# psu_and_discharge.net
KiCad netlist of a schematic drawn in Altium Designer
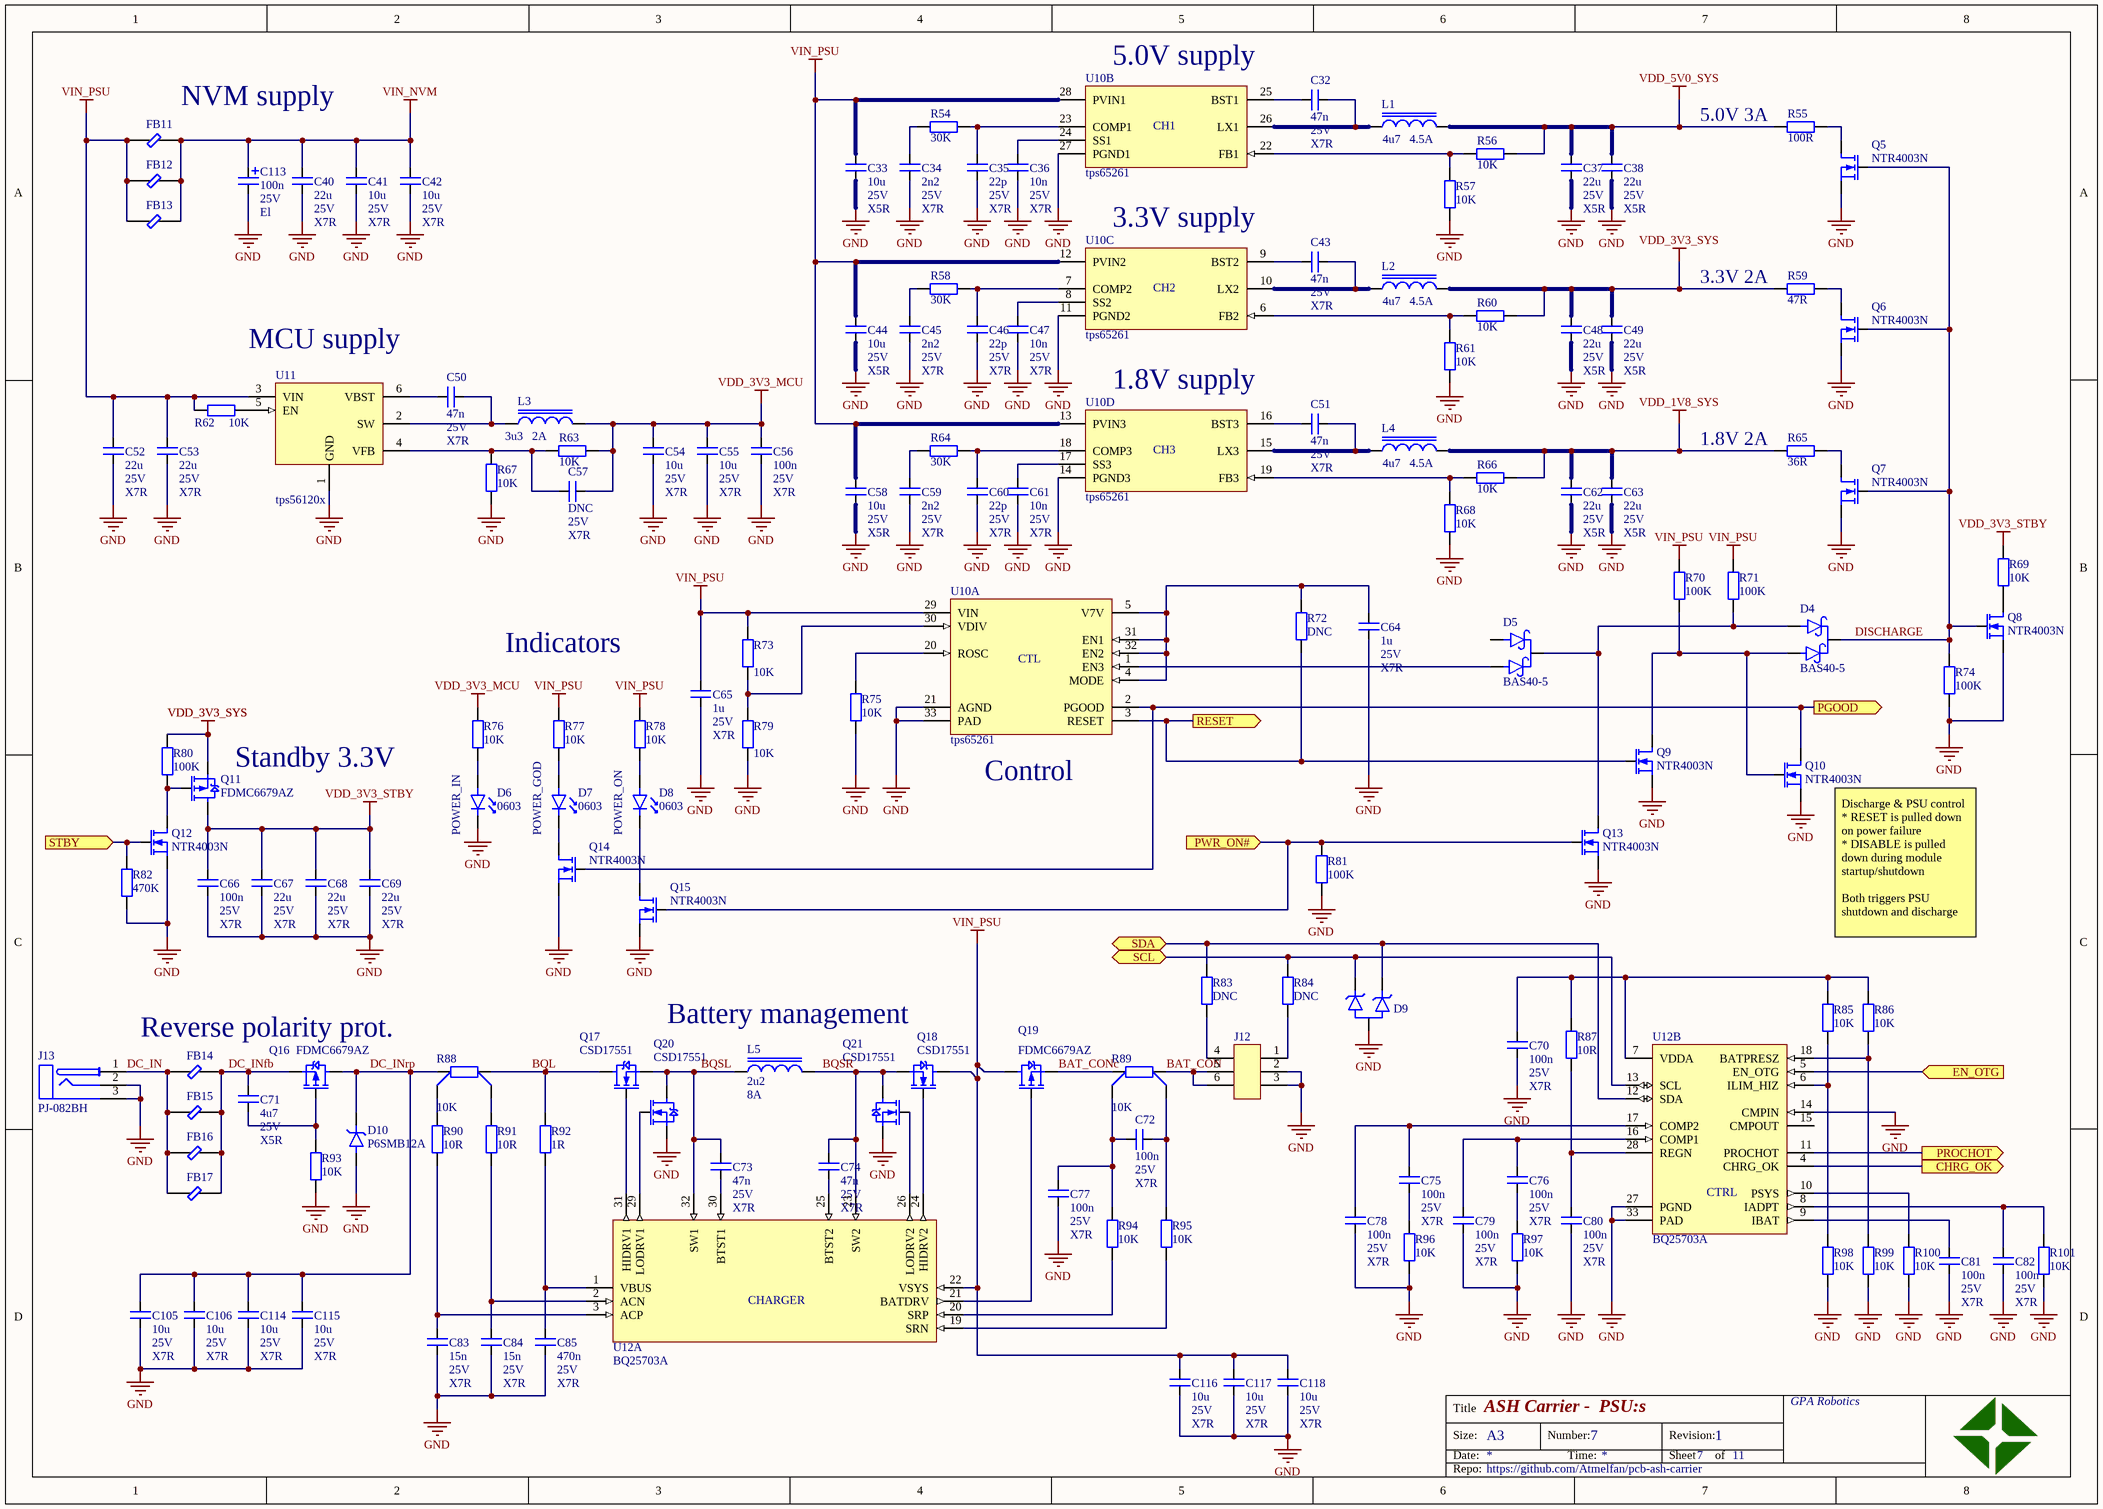
[diagram p0: psu_and_discharge.SchDoc]

(export (version "E")
  (design (tool "Eeschema 10.0.6"))
  (components
    (comp (ref "C32")
      (value "47n")
      (footprint "C1005[0402]")
      (description "Capacitor")
      (fields (field (name "VOLTAGE") "25V") (field (name "TYPE") "X7R") (field (name "Comment") "cap"))
      (libsource (lib "gpa_passives") (part "cap"))
    )
    (comp (ref "C33")
      (value "10u")
      (footprint "C3216[1206]")
      (description "Capacitor")
      (fields (field (name "VOLTAGE") "25V") (field (name "TYPE") "X5R") (field (name "Comment") "cap"))
      (libsource (lib "gpa_passives") (part "cap"))
    )
    (comp (ref "C34")
      (value "2n2")
      (footprint "C1005[0402]")
      (description "Capacitor")
      (fields (field (name "VOLTAGE") "25V") (field (name "TYPE") "X7R") (field (name "Comment") "cap"))
      (libsource (lib "gpa_passives") (part "cap"))
    )
    (comp (ref "C35")
      (value "22p")
      (footprint "C1005[0402]")
      (description "Capacitor")
      (fields (field (name "VOLTAGE") "25V") (field (name "TYPE") "X7R") (field (name "Comment") "cap"))
      (libsource (lib "gpa_passives") (part "cap"))
    )
    (comp (ref "C36")
      (value "10n")
      (footprint "C1005[0402]")
      (description "Capacitor")
      (fields (field (name "VOLTAGE") "25V") (field (name "TYPE") "X7R") (field (name "Comment") "cap"))
      (libsource (lib "gpa_passives") (part "cap"))
    )
    (comp (ref "C37")
      (value "22u")
      (footprint "C3216[1206]")
      (description "Capacitor")
      (fields (field (name "VOLTAGE") "25V") (field (name "TYPE") "X5R") (field (name "Comment") "cap"))
      (libsource (lib "gpa_passives") (part "cap"))
    )
    (comp (ref "C38")
      (value "22u")
      (footprint "C3216[1206]")
      (description "Capacitor")
      (fields (field (name "VOLTAGE") "25V") (field (name "TYPE") "X5R") (field (name "Comment") "cap"))
      (libsource (lib "gpa_passives") (part "cap"))
    )
    (comp (ref "C40")
      (value "22u")
      (footprint "C3216[1206]")
      (description "Capacitor")
      (fields (field (name "VOLTAGE") "25V") (field (name "TYPE") "X7R") (field (name "Comment") "cap"))
      (libsource (lib "gpa_passives") (part "cap"))
    )
    (comp (ref "C41")
      (value "10u")
      (footprint "C3216[1206]")
      (description "Capacitor")
      (fields (field (name "VOLTAGE") "25V") (field (name "TYPE") "X7R") (field (name "Comment") "cap"))
      (libsource (lib "gpa_passives") (part "cap"))
    )
    (comp (ref "C42")
      (value "10u")
      (footprint "C3216[1206]")
      (description "Capacitor")
      (fields (field (name "VOLTAGE") "25V") (field (name "TYPE") "X7R") (field (name "Comment") "cap"))
      (libsource (lib "gpa_passives") (part "cap"))
    )
    (comp (ref "C43")
      (value "47n")
      (footprint "C1005[0402]")
      (description "Capacitor")
      (fields (field (name "VOLTAGE") "25V") (field (name "TYPE") "X7R") (field (name "Comment") "cap"))
      (libsource (lib "gpa_passives") (part "cap"))
    )
    (comp (ref "C44")
      (value "10u")
      (footprint "C3216[1206]")
      (description "Capacitor")
      (fields (field (name "VOLTAGE") "25V") (field (name "TYPE") "X5R") (field (name "Comment") "cap"))
      (libsource (lib "gpa_passives") (part "cap"))
    )
    (comp (ref "C45")
      (value "2n2")
      (footprint "C1005[0402]")
      (description "Capacitor")
      (fields (field (name "VOLTAGE") "25V") (field (name "TYPE") "X7R") (field (name "Comment") "cap"))
      (libsource (lib "gpa_passives") (part "cap"))
    )
    (comp (ref "C46")
      (value "22p")
      (footprint "C1005[0402]")
      (description "Capacitor")
      (fields (field (name "VOLTAGE") "25V") (field (name "TYPE") "X7R") (field (name "Comment") "cap"))
      (libsource (lib "gpa_passives") (part "cap"))
    )
    (comp (ref "C47")
      (value "10n")
      (footprint "C1005[0402]")
      (description "Capacitor")
      (fields (field (name "VOLTAGE") "25V") (field (name "TYPE") "X7R") (field (name "Comment") "cap"))
      (libsource (lib "gpa_passives") (part "cap"))
    )
    (comp (ref "C48")
      (value "22u")
      (footprint "C3216[1206]")
      (description "Capacitor")
      (fields (field (name "VOLTAGE") "25V") (field (name "TYPE") "X5R") (field (name "Comment") "cap"))
      (libsource (lib "gpa_passives") (part "cap"))
    )
    (comp (ref "C49")
      (value "22u")
      (footprint "C3216[1206]")
      (description "Capacitor")
      (fields (field (name "VOLTAGE") "25V") (field (name "TYPE") "X5R") (field (name "Comment") "cap"))
      (libsource (lib "gpa_passives") (part "cap"))
    )
    (comp (ref "C50")
      (value "47n")
      (footprint "C1005[0402]")
      (description "Capacitor")
      (fields (field (name "VOLTAGE") "25V") (field (name "TYPE") "X7R") (field (name "Comment") "cap"))
      (libsource (lib "gpa_passives") (part "cap"))
    )
    (comp (ref "C51")
      (value "47n")
      (footprint "C1005[0402]")
      (description "Capacitor")
      (fields (field (name "VOLTAGE") "25V") (field (name "TYPE") "X7R") (field (name "Comment") "cap"))
      (libsource (lib "gpa_passives") (part "cap"))
    )
    (comp (ref "C52")
      (value "22u")
      (footprint "C3216[1206]")
      (description "Capacitor")
      (fields (field (name "VOLTAGE") "25V") (field (name "TYPE") "X7R") (field (name "Comment") "cap"))
      (libsource (lib "gpa_passives") (part "cap"))
    )
    (comp (ref "C53")
      (value "22u")
      (footprint "C3216[1206]")
      (description "Capacitor")
      (fields (field (name "VOLTAGE") "25V") (field (name "TYPE") "X7R") (field (name "Comment") "cap"))
      (libsource (lib "gpa_passives") (part "cap"))
    )
    (comp (ref "C54")
      (value "10u")
      (footprint "C3216[1206]")
      (description "Capacitor")
      (fields (field (name "VOLTAGE") "25V") (field (name "TYPE") "X7R") (field (name "Comment") "cap"))
      (libsource (lib "gpa_passives") (part "cap"))
    )
    (comp (ref "C55")
      (value "10u")
      (footprint "C3216[1206]")
      (description "Capacitor")
      (fields (field (name "VOLTAGE") "25V") (field (name "TYPE") "X7R") (field (name "Comment") "cap"))
      (libsource (lib "gpa_passives") (part "cap"))
    )
    (comp (ref "C56")
      (value "100n")
      (footprint "C1005[0402]")
      (description "Capacitor")
      (fields (field (name "VOLTAGE") "25V") (field (name "TYPE") "X7R") (field (name "Comment") "cap"))
      (libsource (lib "gpa_passives") (part "cap"))
    )
    (comp (ref "C57")
      (value "DNC")
      (footprint "C1005[0402]")
      (description "Capacitor")
      (fields (field (name "VOLTAGE") "25V") (field (name "TYPE") "X7R") (field (name "Comment") "cap"))
      (libsource (lib "gpa_passives") (part "cap"))
    )
    (comp (ref "C58")
      (value "10u")
      (footprint "C3216[1206]")
      (description "Capacitor")
      (fields (field (name "VOLTAGE") "25V") (field (name "TYPE") "X5R") (field (name "Comment") "cap"))
      (libsource (lib "gpa_passives") (part "cap"))
    )
    (comp (ref "C59")
      (value "2n2")
      (footprint "C1005[0402]")
      (description "Capacitor")
      (fields (field (name "VOLTAGE") "25V") (field (name "TYPE") "X7R") (field (name "Comment") "cap"))
      (libsource (lib "gpa_passives") (part "cap"))
    )
    (comp (ref "C60")
      (value "22p")
      (footprint "C1005[0402]")
      (description "Capacitor")
      (fields (field (name "VOLTAGE") "25V") (field (name "TYPE") "X7R") (field (name "Comment") "cap"))
      (libsource (lib "gpa_passives") (part "cap"))
    )
    (comp (ref "C61")
      (value "10n")
      (footprint "C1005[0402]")
      (description "Capacitor")
      (fields (field (name "VOLTAGE") "25V") (field (name "TYPE") "X7R") (field (name "Comment") "cap"))
      (libsource (lib "gpa_passives") (part "cap"))
    )
    (comp (ref "C62")
      (value "22u")
      (footprint "C3216[1206]")
      (description "Capacitor")
      (fields (field (name "VOLTAGE") "25V") (field (name "TYPE") "X5R") (field (name "Comment") "cap"))
      (libsource (lib "gpa_passives") (part "cap"))
    )
    (comp (ref "C63")
      (value "22u")
      (footprint "C3216[1206]")
      (description "Capacitor")
      (fields (field (name "VOLTAGE") "25V") (field (name "TYPE") "X5R") (field (name "Comment") "cap"))
      (libsource (lib "gpa_passives") (part "cap"))
    )
    (comp (ref "C64")
      (value "1u")
      (footprint "C2012[0805]")
      (description "Capacitor")
      (fields (field (name "VOLTAGE") "25V") (field (name "TYPE") "X7R") (field (name "Comment") "cap"))
      (libsource (lib "gpa_passives") (part "cap"))
    )
    (comp (ref "C65")
      (value "1u")
      (footprint "C2012[0805]")
      (description "Capacitor")
      (fields (field (name "VOLTAGE") "25V") (field (name "TYPE") "X7R") (field (name "Comment") "cap"))
      (libsource (lib "gpa_passives") (part "cap"))
    )
    (comp (ref "C66")
      (value "100n")
      (footprint "C1005[0402]")
      (description "Capacitor")
      (fields (field (name "VOLTAGE") "25V") (field (name "TYPE") "X7R") (field (name "Comment") "cap"))
      (libsource (lib "gpa_passives") (part "cap"))
    )
    (comp (ref "C67")
      (value "22u")
      (footprint "C3216[1206]")
      (description "Capacitor")
      (fields (field (name "VOLTAGE") "25V") (field (name "TYPE") "X7R") (field (name "Comment") "cap"))
      (libsource (lib "gpa_passives") (part "cap"))
    )
    (comp (ref "C68")
      (value "22u")
      (footprint "C3216[1206]")
      (description "Capacitor")
      (fields (field (name "VOLTAGE") "25V") (field (name "TYPE") "X7R") (field (name "Comment") "cap"))
      (libsource (lib "gpa_passives") (part "cap"))
    )
    (comp (ref "C69")
      (value "22u")
      (footprint "C3216[1206]")
      (description "Capacitor")
      (fields (field (name "VOLTAGE") "25V") (field (name "TYPE") "X7R") (field (name "Comment") "cap"))
      (libsource (lib "gpa_passives") (part "cap"))
    )
    (comp (ref "C70")
      (value "100n")
      (footprint "C1005[0402]")
      (description "Capacitor")
      (fields (field (name "VOLTAGE") "25V") (field (name "TYPE") "X7R") (field (name "Comment") "cap"))
      (libsource (lib "gpa_passives") (part "cap"))
    )
    (comp (ref "C71")
      (value "4u7")
      (footprint "C1005[0402]")
      (description "Capacitor")
      (fields (field (name "VOLTAGE") "25V") (field (name "TYPE") "X5R") (field (name "Comment") "cap"))
      (libsource (lib "gpa_passives") (part "cap"))
    )
    (comp (ref "C72")
      (value "100n")
      (footprint "C1005[0402]")
      (description "Capacitor")
      (fields (field (name "VOLTAGE") "25V") (field (name "TYPE") "X7R") (field (name "Comment") "cap"))
      (libsource (lib "gpa_passives") (part "cap"))
    )
    (comp (ref "C73")
      (value "47n")
      (footprint "C1005[0402]")
      (description "Capacitor")
      (fields (field (name "VOLTAGE") "25V") (field (name "TYPE") "X7R") (field (name "Comment") "cap"))
      (libsource (lib "gpa_passives") (part "cap"))
    )
    (comp (ref "C74")
      (value "47n")
      (footprint "C1005[0402]")
      (description "Capacitor")
      (fields (field (name "VOLTAGE") "25V") (field (name "TYPE") "X7R") (field (name "Comment") "cap"))
      (libsource (lib "gpa_passives") (part "cap"))
    )
    (comp (ref "C75")
      (value "100n")
      (footprint "C1005[0402]")
      (description "Capacitor")
      (fields (field (name "VOLTAGE") "25V") (field (name "TYPE") "X7R") (field (name "Comment") "cap"))
      (libsource (lib "gpa_passives") (part "cap"))
    )
    (comp (ref "C76")
      (value "100n")
      (footprint "C1005[0402]")
      (description "Capacitor")
      (fields (field (name "VOLTAGE") "25V") (field (name "TYPE") "X7R") (field (name "Comment") "cap"))
      (libsource (lib "gpa_passives") (part "cap"))
    )
    (comp (ref "C77")
      (value "100n")
      (footprint "C1005[0402]")
      (description "Capacitor")
      (fields (field (name "VOLTAGE") "25V") (field (name "TYPE") "X7R") (field (name "Comment") "cap"))
      (libsource (lib "gpa_passives") (part "cap"))
    )
    (comp (ref "C78")
      (value "100n")
      (footprint "C1005[0402]")
      (description "Capacitor")
      (fields (field (name "VOLTAGE") "25V") (field (name "TYPE") "X7R") (field (name "Comment") "cap"))
      (libsource (lib "gpa_passives") (part "cap"))
    )
    (comp (ref "C79")
      (value "100n")
      (footprint "C1005[0402]")
      (description "Capacitor")
      (fields (field (name "VOLTAGE") "25V") (field (name "TYPE") "X7R") (field (name "Comment") "cap"))
      (libsource (lib "gpa_passives") (part "cap"))
    )
    (comp (ref "C80")
      (value "100n")
      (footprint "C1005[0402]")
      (description "Capacitor")
      (fields (field (name "VOLTAGE") "25V") (field (name "TYPE") "X7R") (field (name "Comment") "cap"))
      (libsource (lib "gpa_passives") (part "cap"))
    )
    (comp (ref "C81")
      (value "100n")
      (footprint "C1005[0402]")
      (description "Capacitor")
      (fields (field (name "VOLTAGE") "25V") (field (name "TYPE") "X7R") (field (name "Comment") "cap"))
      (libsource (lib "gpa_passives") (part "cap"))
    )
    (comp (ref "C82")
      (value "100n")
      (footprint "C1005[0402]")
      (description "Capacitor")
      (fields (field (name "VOLTAGE") "25V") (field (name "TYPE") "X7R") (field (name "Comment") "cap"))
      (libsource (lib "gpa_passives") (part "cap"))
    )
    (comp (ref "C83")
      (value "15n")
      (footprint "C1005[0402]")
      (description "Capacitor")
      (fields (field (name "VOLTAGE") "25V") (field (name "TYPE") "X7R") (field (name "Comment") "cap"))
      (libsource (lib "gpa_passives") (part "cap"))
    )
    (comp (ref "C84")
      (value "15n")
      (footprint "C1005[0402]")
      (description "Capacitor")
      (fields (field (name "VOLTAGE") "25V") (field (name "TYPE") "X7R") (field (name "Comment") "cap"))
      (libsource (lib "gpa_passives") (part "cap"))
    )
    (comp (ref "C85")
      (value "470n")
      (footprint "C1005[0402]")
      (description "Capacitor")
      (fields (field (name "VOLTAGE") "25V") (field (name "TYPE") "X7R") (field (name "Comment") "cap"))
      (libsource (lib "gpa_passives") (part "cap"))
    )
    (comp (ref "C105")
      (value "10u")
      (footprint "C3216[1206]")
      (description "Capacitor")
      (fields (field (name "VOLTAGE") "25V") (field (name "TYPE") "X7R") (field (name "Comment") "cap"))
      (libsource (lib "gpa_passives") (part "cap"))
    )
    (comp (ref "C106")
      (value "10u")
      (footprint "C3216[1206]")
      (description "Capacitor")
      (fields (field (name "VOLTAGE") "25V") (field (name "TYPE") "X7R") (field (name "Comment") "cap"))
      (libsource (lib "gpa_passives") (part "cap"))
    )
    (comp (ref "C113")
      (value "100n")
      (footprint "CAPAE7366X55M")
      (description "Polarized capacitor")
      (fields (field (name "VOLTAGE") "25V") (field (name "TYPE") "El") (field (name "Comment") "pcap"))
      (libsource (lib "gpa_passives") (part "pcap"))
    )
    (comp (ref "C114")
      (value "10u")
      (footprint "C3216[1206]")
      (description "Capacitor")
      (fields (field (name "VOLTAGE") "25V") (field (name "TYPE") "X7R") (field (name "Comment") "cap"))
      (libsource (lib "gpa_passives") (part "cap"))
    )
    (comp (ref "C115")
      (value "10u")
      (footprint "C3216[1206]")
      (description "Capacitor")
      (fields (field (name "VOLTAGE") "25V") (field (name "TYPE") "X7R") (field (name "Comment") "cap"))
      (libsource (lib "gpa_passives") (part "cap"))
    )
    (comp (ref "C116")
      (value "10u")
      (footprint "C3216[1206]")
      (description "Capacitor")
      (fields (field (name "VOLTAGE") "25V") (field (name "TYPE") "X7R") (field (name "Comment") "cap"))
      (libsource (lib "gpa_passives") (part "cap"))
    )
    (comp (ref "C117")
      (value "10u")
      (footprint "C3216[1206]")
      (description "Capacitor")
      (fields (field (name "VOLTAGE") "25V") (field (name "TYPE") "X7R") (field (name "Comment") "cap"))
      (libsource (lib "gpa_passives") (part "cap"))
    )
    (comp (ref "C118")
      (value "10u")
      (footprint "C3216[1206]")
      (description "Capacitor")
      (fields (field (name "VOLTAGE") "25V") (field (name "TYPE") "X7R") (field (name "Comment") "cap"))
      (libsource (lib "gpa_passives") (part "cap"))
    )
    (comp (ref "D4")
      (value "BAS40-5")
      (footprint "DCC_SOT95P235X110-3N")
      (libsource (lib "gpa_actives") (part "diode_dual_cc"))
    )
    (comp (ref "D5")
      (value "BAS40-5")
      (footprint "DCC_SOT95P235X110-3N")
      (libsource (lib "gpa_actives") (part "diode_dual_cc"))
    )
    (comp (ref "D6")
      (value "0603")
      (footprint "LEDC1608X06N")
      (libsource (lib "gpa_actives") (part "diode_led"))
    )
    (comp (ref "D7")
      (value "0603")
      (footprint "LEDC1608X06N")
      (libsource (lib "gpa_actives") (part "diode_led"))
    )
    (comp (ref "D8")
      (value "0603")
      (footprint "LEDC1608X06N")
      (libsource (lib "gpa_actives") (part "diode_led"))
    )
    (comp (ref "D9")
      (value "Zener")
      (footprint "DCA_SOT95P235X110-3N")
      (fields (field (name "VOLTAGE") "3.6V"))
      (libsource (lib "gpa_actives") (part "diode_dual_ca_zener"))
    )
    (comp (ref "D10")
      (value "P6SMB12A")
      (footprint "SMA_DIOM5226X22N")
      (libsource (lib "gpa_actives") (part "diode_tvs_unidirectional"))
    )
    (comp (ref "FB11")
      (value "2506036007Y3")
      (footprint "FBC1608X07N")
      (description "Ferrite bead")
      (libsource (lib "gpa_passives") (part "ferrite_bead"))
    )
    (comp (ref "FB12")
      (value "2506036007Y3")
      (footprint "FBC1608X07N")
      (description "Ferrite bead")
      (libsource (lib "gpa_passives") (part "ferrite_bead"))
    )
    (comp (ref "FB13")
      (value "2506036007Y3")
      (footprint "FBC1608X07N")
      (description "Ferrite bead")
      (libsource (lib "gpa_passives") (part "ferrite_bead"))
    )
    (comp (ref "FB14")
      (value "2506036007Y3")
      (footprint "FBC1608X07N")
      (description "Ferrite bead")
      (libsource (lib "gpa_passives") (part "ferrite_bead"))
    )
    (comp (ref "FB15")
      (value "2506036007Y3")
      (footprint "FBC1608X07N")
      (description "Ferrite bead")
      (libsource (lib "gpa_passives") (part "ferrite_bead"))
    )
    (comp (ref "FB16")
      (value "2506036007Y3")
      (footprint "FBC1608X07N")
      (description "Ferrite bead")
      (libsource (lib "gpa_passives") (part "ferrite_bead"))
    )
    (comp (ref "FB17")
      (value "2506036007Y3")
      (footprint "FBC1608X07N")
      (description "Ferrite bead")
      (libsource (lib "gpa_passives") (part "ferrite_bead"))
    )
    (comp (ref "J12")
      (value "43045-0600")
      (footprint "molex_microfit_2x6_90deg")
      (libsource (lib "gpa_connectors") (part "microfit_2x3"))
    )
    (comp (ref "J13")
      (value "PJ-082BH")
      (footprint "CUI_DC_5.5MM_PJ028")
      (libsource (lib "gpa_connectors") (part "dc_jack_shielded"))
    )
    (comp (ref "L1")
      (value "4u7")
      (footprint "BOURNS_SRN6045TA-XXX")
      (fields (field (name "CURRENT") "4.5A") (field (name "Comment") "ASPI-0630LR-XXXM-T15"))
      (libsource (lib "gpa_passives") (part "ind"))
    )
    (comp (ref "L2")
      (value "4u7")
      (footprint "BOURNS_SRN6045TA-XXX")
      (fields (field (name "CURRENT") "4.5A") (field (name "Comment") "ASPI-0630LR-XXXM-T15"))
      (libsource (lib "gpa_passives") (part "ind"))
    )
    (comp (ref "L3")
      (value "3u3")
      (footprint "YUDEN_NRS4018T-XXXMDGJ")
      (fields (field (name "CURRENT") "2A") (field (name "Comment") "ASPI-0630LR-XXXM-T15"))
      (libsource (lib "gpa_passives") (part "ind"))
    )
    (comp (ref "L4")
      (value "4u7")
      (footprint "BOURNS_SRN6045TA-XXX")
      (fields (field (name "CURRENT") "4.5A") (field (name "Comment") "ASPI-0630LR-XXXM-T15"))
      (libsource (lib "gpa_passives") (part "ind"))
    )
    (comp (ref "L5")
      (value "2u2")
      (footprint "VISHAY_IHLM2525CZERXXXM01")
      (fields (field (name "CURRENT") "8A") (field (name "Comment") "ASPI-0630LR-XXXM-T15"))
      (libsource (lib "gpa_passives") (part "ind"))
    )
    (comp (ref "Q5")
      (value "NTR4003N")
      (footprint "NCH_SOT95P237X110-3N")
      (libsource (lib "gpa_actives") (part "nch_mosfet"))
    )
    (comp (ref "Q6")
      (value "NTR4003N")
      (footprint "NCH_SOT95P237X110-3N")
      (libsource (lib "gpa_actives") (part "nch_mosfet"))
    )
    (comp (ref "Q7")
      (value "NTR4003N")
      (footprint "NCH_SOT95P237X110-3N")
      (libsource (lib "gpa_actives") (part "nch_mosfet"))
    )
    (comp (ref "Q8")
      (value "NTR4003N")
      (footprint "NCH_SOT95P237X110-3N")
      (libsource (lib "gpa_actives") (part "nch_mosfet"))
    )
    (comp (ref "Q9")
      (value "NTR4003N")
      (footprint "NCH_SOT95P237X110-3N")
      (libsource (lib "gpa_actives") (part "nch_mosfet"))
    )
    (comp (ref "Q10")
      (value "NTR4003N")
      (footprint "NCH_SOT95P237X110-3N")
      (libsource (lib "gpa_actives") (part "nch_mosfet"))
    )
    (comp (ref "Q11")
      (value "FDMC6679AZ")
      (footprint "NCH_SON65P330X80_HS-9N")
      (libsource (lib "gpa_actives") (part "pch_mosfet_diode"))
    )
    (comp (ref "Q12")
      (value "NTR4003N")
      (footprint "NCH_SOT95P237X110-3N")
      (libsource (lib "gpa_actives") (part "nch_mosfet"))
    )
    (comp (ref "Q13")
      (value "NTR4003N")
      (footprint "NCH_SOT95P237X110-3N")
      (libsource (lib "gpa_actives") (part "nch_mosfet"))
    )
    (comp (ref "Q14")
      (value "NTR4003N")
      (footprint "NCH_SOT95P237X110-3N")
      (libsource (lib "gpa_actives") (part "nch_mosfet"))
    )
    (comp (ref "Q15")
      (value "NTR4003N")
      (footprint "NCH_SOT95P237X110-3N")
      (libsource (lib "gpa_actives") (part "nch_mosfet"))
    )
    (comp (ref "Q16")
      (value "FDMC6679AZ")
      (footprint "NCH_SON65P330X80_HS-9N")
      (libsource (lib "gpa_actives") (part "pch_mosfet_diode"))
    )
    (comp (ref "Q17")
      (value "CSD17551")
      (footprint "NCH_SON65P330X80_HS-9N")
      (libsource (lib "gpa_actives") (part "nch_mosfet_diode"))
    )
    (comp (ref "Q18")
      (value "CSD17551")
      (footprint "NCH_SON65P330X80_HS-9N")
      (libsource (lib "gpa_actives") (part "nch_mosfet_diode"))
    )
    (comp (ref "Q19")
      (value "FDMC6679AZ")
      (footprint "NCH_SON65P330X80_HS-9N")
      (libsource (lib "gpa_actives") (part "pch_mosfet_diode"))
    )
    (comp (ref "Q20")
      (value "CSD17551")
      (footprint "NCH_SON65P330X80_HS-9N")
      (libsource (lib "gpa_actives") (part "nch_mosfet_diode"))
    )
    (comp (ref "Q21")
      (value "CSD17551")
      (footprint "NCH_SON65P330X80_HS-9N")
      (libsource (lib "gpa_actives") (part "nch_mosfet_diode"))
    )
    (comp (ref "R54")
      (value "30K")
      (footprint "R1005[0402]")
      (description "Resistor")
      (fields (field (name "Comment") "res"))
      (libsource (lib "") (part "res_1"))
    )
    (comp (ref "R55")
      (value "100R")
      (footprint "R1005[0402]")
      (description "Resistor")
      (fields (field (name "Comment") "res"))
      (libsource (lib "") (part "res_1"))
    )
    (comp (ref "R56")
      (value "10K")
      (footprint "R1005[0402]")
      (description "Resistor")
      (fields (field (name "Comment") "res"))
      (libsource (lib "") (part "res_3"))
    )
    (comp (ref "R57")
      (value "10K")
      (footprint "R1005[0402]")
      (description "Resistor")
      (fields (field (name "Comment") "res"))
      (libsource (lib "gpa_passives") (part "res"))
    )
    (comp (ref "R58")
      (value "30K")
      (footprint "R1005[0402]")
      (description "Resistor")
      (fields (field (name "Comment") "res"))
      (libsource (lib "") (part "res_1"))
    )
    (comp (ref "R59")
      (value "47R")
      (footprint "R1005[0402]")
      (description "Resistor")
      (fields (field (name "Comment") "res"))
      (libsource (lib "") (part "res_1"))
    )
    (comp (ref "R60")
      (value "10K")
      (footprint "R1005[0402]")
      (description "Resistor")
      (fields (field (name "Comment") "res"))
      (libsource (lib "") (part "res_3"))
    )
    (comp (ref "R61")
      (value "10K")
      (footprint "R1005[0402]")
      (description "Resistor")
      (fields (field (name "Comment") "res"))
      (libsource (lib "gpa_passives") (part "res"))
    )
    (comp (ref "R62")
      (value "10K")
      (footprint "R1005[0402]")
      (description "Resistor")
      (fields (field (name "Comment") "res"))
      (libsource (lib "") (part "res_1"))
    )
    (comp (ref "R63")
      (value "10K")
      (footprint "R1005[0402]")
      (description "Resistor")
      (fields (field (name "Comment") "res"))
      (libsource (lib "") (part "res_1"))
    )
    (comp (ref "R64")
      (value "30K")
      (footprint "R1005[0402]")
      (description "Resistor")
      (fields (field (name "Comment") "res"))
      (libsource (lib "") (part "res_1"))
    )
    (comp (ref "R65")
      (value "36R")
      (footprint "R1005[0402]")
      (description "Resistor")
      (fields (field (name "Comment") "res"))
      (libsource (lib "") (part "res_1"))
    )
    (comp (ref "R66")
      (value "10K")
      (footprint "R1005[0402]")
      (description "Resistor")
      (fields (field (name "Comment") "res"))
      (libsource (lib "") (part "res_3"))
    )
    (comp (ref "R67")
      (value "10K")
      (footprint "R1005[0402]")
      (description "Resistor")
      (fields (field (name "Comment") "res"))
      (libsource (lib "") (part "res_2"))
    )
    (comp (ref "R68")
      (value "10K")
      (footprint "R1005[0402]")
      (description "Resistor")
      (fields (field (name "Comment") "res"))
      (libsource (lib "gpa_passives") (part "res"))
    )
    (comp (ref "R69")
      (value "10K")
      (footprint "R1005[0402]")
      (description "Resistor")
      (fields (field (name "Comment") "res"))
      (libsource (lib "") (part "res_2"))
    )
    (comp (ref "R70")
      (value "100K")
      (footprint "R1005[0402]")
      (description "Resistor")
      (fields (field (name "Comment") "res"))
      (libsource (lib "gpa_passives") (part "res"))
    )
    (comp (ref "R71")
      (value "100K")
      (footprint "R1005[0402]")
      (description "Resistor")
      (fields (field (name "Comment") "res"))
      (libsource (lib "gpa_passives") (part "res"))
    )
    (comp (ref "R72")
      (value "DNC")
      (footprint "R1005[0402]")
      (description "Resistor")
      (fields (field (name "Comment") "res"))
      (libsource (lib "gpa_passives") (part "res"))
    )
    (comp (ref "R73")
      (value "10K")
      (footprint "R1005[0402]")
      (description "Resistor")
      (fields (field (name "Comment") "res"))
      (libsource (lib "") (part "res_2"))
    )
    (comp (ref "R74")
      (value "100K")
      (footprint "R1005[0402]")
      (description "Resistor")
      (fields (field (name "Comment") "res"))
      (libsource (lib "") (part "res_2"))
    )
    (comp (ref "R75")
      (value "10K")
      (footprint "R1005[0402]")
      (description "Resistor")
      (fields (field (name "Comment") "res"))
      (libsource (lib "") (part "res_2"))
    )
    (comp (ref "R76")
      (value "10K")
      (footprint "R1005[0402]")
      (description "Resistor")
      (fields (field (name "Comment") "res"))
      (libsource (lib "") (part "res_2"))
    )
    (comp (ref "R77")
      (value "10K")
      (footprint "R1005[0402]")
      (description "Resistor")
      (fields (field (name "Comment") "res"))
      (libsource (lib "") (part "res_2"))
    )
    (comp (ref "R78")
      (value "10K")
      (footprint "R1005[0402]")
      (description "Resistor")
      (fields (field (name "Comment") "res"))
      (libsource (lib "") (part "res_2"))
    )
    (comp (ref "R79")
      (value "10K")
      (footprint "R1005[0402]")
      (description "Resistor")
      (fields (field (name "Comment") "res"))
      (libsource (lib "") (part "res_2"))
    )
    (comp (ref "R80")
      (value "100K")
      (footprint "R1005[0402]")
      (description "Resistor")
      (fields (field (name "Comment") "res"))
      (libsource (lib "") (part "res_2"))
    )
    (comp (ref "R81")
      (value "100K")
      (footprint "R1005[0402]")
      (description "Resistor")
      (fields (field (name "Comment") "res"))
      (libsource (lib "gpa_passives") (part "res"))
    )
    (comp (ref "R82")
      (value "470K")
      (footprint "R1005[0402]")
      (description "Resistor")
      (fields (field (name "Comment") "res"))
      (libsource (lib "") (part "res_2"))
    )
    (comp (ref "R83")
      (value "DNC")
      (footprint "R1005[0402]")
      (description "Resistor")
      (fields (field (name "Comment") "res"))
      (libsource (lib "gpa_passives") (part "res"))
    )
    (comp (ref "R84")
      (value "DNC")
      (footprint "R1005[0402]")
      (description "Resistor")
      (fields (field (name "Comment") "res"))
      (libsource (lib "gpa_passives") (part "res"))
    )
    (comp (ref "R85")
      (value "10K")
      (footprint "R1005[0402]")
      (description "Resistor")
      (fields (field (name "Comment") "res"))
      (libsource (lib "gpa_passives") (part "res"))
    )
    (comp (ref "R86")
      (value "10K")
      (footprint "R1005[0402]")
      (description "Resistor")
      (fields (field (name "Comment") "res"))
      (libsource (lib "gpa_passives") (part "res"))
    )
    (comp (ref "R87")
      (value "10R")
      (footprint "R1005[0402]")
      (description "Resistor")
      (fields (field (name "Comment") "res"))
      (libsource (lib "") (part "res_2"))
    )
    (comp (ref "R88")
      (value "10K")
      (footprint "4W_R320P320X90-4N")
      (description "Resistor")
      (fields (field (name "Comment") "res_sens"))
      (libsource (lib "") (part "res_sens_1"))
    )
    (comp (ref "R89")
      (value "10K")
      (footprint "4W_R320P320X90-4N")
      (description "Resistor")
      (fields (field (name "Comment") "res_sens"))
      (libsource (lib "gpa_passives") (part "res_sens"))
    )
    (comp (ref "R90")
      (value "10R")
      (footprint "R1005[0402]")
      (description "Resistor")
      (fields (field (name "Comment") "res"))
      (libsource (lib "") (part "res_2"))
    )
    (comp (ref "R91")
      (value "10R")
      (footprint "R1005[0402]")
      (description "Resistor")
      (fields (field (name "Comment") "res"))
      (libsource (lib "") (part "res_2"))
    )
    (comp (ref "R92")
      (value "1R")
      (footprint "R1005[0402]")
      (description "Resistor")
      (fields (field (name "Comment") "res"))
      (libsource (lib "") (part "res_2"))
    )
    (comp (ref "R93")
      (value "10K")
      (footprint "R1005[0402]")
      (description "Resistor")
      (fields (field (name "Comment") "res"))
      (libsource (lib "") (part "res_2"))
    )
    (comp (ref "R94")
      (value "10K")
      (footprint "R1005[0402]")
      (description "Resistor")
      (fields (field (name "Comment") "res"))
      (libsource (lib "") (part "res_2"))
    )
    (comp (ref "R95")
      (value "10K")
      (footprint "R1005[0402]")
      (description "Resistor")
      (fields (field (name "Comment") "res"))
      (libsource (lib "") (part "res_2"))
    )
    (comp (ref "R96")
      (value "10K")
      (footprint "R1005[0402]")
      (description "Resistor")
      (fields (field (name "Comment") "res"))
      (libsource (lib "") (part "res_2"))
    )
    (comp (ref "R97")
      (value "10K")
      (footprint "R1005[0402]")
      (description "Resistor")
      (fields (field (name "Comment") "res"))
      (libsource (lib "") (part "res_2"))
    )
    (comp (ref "R98")
      (value "10K")
      (footprint "R1005[0402]")
      (description "Resistor")
      (fields (field (name "Comment") "res"))
      (libsource (lib "gpa_passives") (part "res"))
    )
    (comp (ref "R99")
      (value "10K")
      (footprint "R1005[0402]")
      (description "Resistor")
      (fields (field (name "Comment") "res"))
      (libsource (lib "gpa_passives") (part "res"))
    )
    (comp (ref "R100")
      (value "10K")
      (footprint "R1005[0402]")
      (description "Resistor")
      (fields (field (name "Comment") "res"))
      (libsource (lib "") (part "res_2"))
    )
    (comp (ref "R101")
      (value "10K")
      (footprint "R1005[0402]")
      (description "Resistor")
      (fields (field (name "Comment") "res"))
      (libsource (lib "") (part "res_2"))
    )
    (comp (ref "U10")
      (value "tps65261")
      (footprint "TI_QFN50P500X500X100_HS-33M")
      (libsource (lib "gpa_ti") (part "tps65261"))
    )
    (comp (ref "U11")
      (value "tps56120x")
      (footprint "TI_SOT95P280X110-6N")
      (libsource (lib "gpa_ti") (part "tps56120x"))
    )
    (comp (ref "U12")
      (value "BQ25703A")
      (footprint "TI_QFN40P400X400X80_HS-33M")
      (libsource (lib "gpa_ti") (part "bq25703a"))
    )
  )
  (nets
    (net (code "1") (name "/BAT_CON") (class "Default")
      (node (ref "J12") (pin "5") (pintype "passive"))
      (node (ref "J12") (pin "6") (pintype "passive"))
      (node (ref "R89") (pin "2") (pinfunction "2_2") (pintype "passive"))
    )
    (net (code "2") (name "/BAT_CONc") (class "Default")
      (node (ref "Q19") (pin "S") (pinfunction "S_S") (pintype "passive"))
      (node (ref "R89") (pin "1") (pinfunction "1_1") (pintype "passive"))
    )
    (net (code "3") (name "/BQL") (class "Default")
      (node (ref "Q17") (pin "D") (pinfunction "D_D") (pintype "passive"))
      (node (ref "R88") (pin "1") (pinfunction "1_1") (pintype "passive"))
      (node (ref "R92") (pin "2") (pinfunction "2_2") (pintype "passive"))
    )
    (net (code "4") (name "/BQSL") (class "Default")
      (node (ref "C73") (pin "2") (pinfunction "2_2") (pintype "passive"))
      (node (ref "L5") (pin "1") (pinfunction "1_1") (pintype "passive"))
      (node (ref "Q17") (pin "S") (pinfunction "S_S") (pintype "passive"))
      (node (ref "Q20") (pin "D") (pinfunction "D_D") (pintype "passive"))
      (node (ref "U12") (pin "32") (pinfunction "SW1_32") (pintype "input"))
    )
    (net (code "5") (name "/BQSR") (class "Default")
      (node (ref "C74") (pin "2") (pinfunction "2_2") (pintype "passive"))
      (node (ref "L5") (pin "2") (pinfunction "2_2") (pintype "passive"))
      (node (ref "Q18") (pin "S") (pinfunction "S_S") (pintype "passive"))
      (node (ref "Q21") (pin "D") (pinfunction "D_D") (pintype "passive"))
      (node (ref "U12") (pin "23") (pinfunction "SW2_23") (pintype "input"))
    )
    (net (code "6") (name "/CHRG_OK") (class "Default")
      (node (ref "U12") (pin "4") (pinfunction "CHRG_OK_4") (pintype "open_collector"))
    )
    (net (code "7") (name "/DC_IN") (class "Default")
      (node (ref "FB14") (pin "1") (pinfunction "1_1") (pintype "passive"))
      (node (ref "FB15") (pin "1") (pinfunction "1_1") (pintype "passive"))
      (node (ref "FB16") (pin "1") (pinfunction "1_1") (pintype "passive"))
      (node (ref "FB17") (pin "1") (pinfunction "1_1") (pintype "passive"))
      (node (ref "J13") (pin "1") (pinfunction "1_1") (pintype "passive"))
    )
    (net (code "8") (name "/DC_INfb") (class "Default")
      (node (ref "C71") (pin "2") (pinfunction "2_2") (pintype "passive"))
      (node (ref "FB14") (pin "2") (pinfunction "2_2") (pintype "passive"))
      (node (ref "FB15") (pin "2") (pinfunction "2_2") (pintype "passive"))
      (node (ref "FB16") (pin "2") (pinfunction "2_2") (pintype "passive"))
      (node (ref "FB17") (pin "2") (pinfunction "2_2") (pintype "passive"))
      (node (ref "Q16") (pin "S") (pinfunction "S_S") (pintype "passive"))
    )
    (net (code "9") (name "/DC_INrp") (class "Default")
      (node (ref "C105") (pin "2") (pinfunction "2_2") (pintype "passive"))
      (node (ref "C106") (pin "2") (pinfunction "2_2") (pintype "passive"))
      (node (ref "C114") (pin "2") (pinfunction "2_2") (pintype "passive"))
      (node (ref "C115") (pin "2") (pinfunction "2_2") (pintype "passive"))
      (node (ref "D10") (pin "C") (pinfunction "C_C") (pintype "passive"))
      (node (ref "Q16") (pin "D") (pinfunction "D_D") (pintype "passive"))
      (node (ref "R88") (pin "2") (pinfunction "2_2") (pintype "passive"))
    )
    (net (code "10") (name "/DISCHARGE") (class "Default")
      (node (ref "D4") (pin "C") (pinfunction "C_C") (pintype "passive"))
      (node (ref "Q5") (pin "G") (pinfunction "G_G") (pintype "passive"))
      (node (ref "Q6") (pin "G") (pinfunction "G_G") (pintype "passive"))
      (node (ref "Q7") (pin "G") (pinfunction "G_G") (pintype "passive"))
      (node (ref "Q8") (pin "G") (pinfunction "G_G") (pintype "passive"))
      (node (ref "R74") (pin "2") (pinfunction "2_2") (pintype "passive"))
    )
    (net (code "11") (name "/EN_OTG") (class "Default")
      (node (ref "U12") (pin "5") (pinfunction "EN_OTG_5") (pintype "input"))
    )
    (net (code "12") (name "/PGOOD") (class "Default")
      (node (ref "Q10") (pin "D") (pinfunction "D_D") (pintype "passive"))
      (node (ref "Q14") (pin "G") (pinfunction "G_G") (pintype "passive"))
      (node (ref "U10") (pin "2") (pinfunction "PGOOD_2") (pintype "open_collector"))
    )
    (net (code "13") (name "/PROCHOT") (class "Default")
      (node (ref "U12") (pin "11") (pinfunction "PROCHOT_11") (pintype "open_collector"))
    )
    (net (code "14") (name "/PWR_ON#") (class "Default")
      (node (ref "Q13") (pin "G") (pinfunction "G_G") (pintype "passive"))
      (node (ref "Q15") (pin "G") (pinfunction "G_G") (pintype "passive"))
      (node (ref "R81") (pin "1") (pinfunction "1_1") (pintype "passive"))
    )
    (net (code "15") (name "/RESET") (class "Default")
      (node (ref "Q9") (pin "G") (pinfunction "G_G") (pintype "passive"))
      (node (ref "R72") (pin "2") (pinfunction "2_2") (pintype "passive"))
      (node (ref "U10") (pin "3") (pinfunction "RESET_3") (pintype "open_collector"))
    )
    (net (code "16") (name "/SCL") (class "Default")
      (node (ref "D9") (pin "C2") (pinfunction "C2_C2") (pintype "passive"))
      (node (ref "R84") (pin "1") (pinfunction "1_1") (pintype "passive"))
      (node (ref "U12") (pin "13") (pinfunction "SCL_13") (pintype "bidirectional"))
    )
    (net (code "17") (name "/SDA") (class "Default")
      (node (ref "D9") (pin "C1") (pinfunction "C1_C1") (pintype "passive"))
      (node (ref "R83") (pin "1") (pinfunction "1_1") (pintype "passive"))
      (node (ref "U12") (pin "12") (pinfunction "SDA_12") (pintype "bidirectional"))
    )
    (net (code "18") (name "/STBY") (class "Default")
      (node (ref "Q12") (pin "G") (pinfunction "G_G") (pintype "passive"))
      (node (ref "R82") (pin "2") (pinfunction "2_2") (pintype "passive"))
    )
    (net (code "19") (name "GND") (class "Default")
      (node (ref "C105") (pin "1") (pinfunction "1_1") (pintype "passive"))
      (node (ref "C106") (pin "1") (pinfunction "1_1") (pintype "passive"))
      (node (ref "C113") (pin "2") (pinfunction "2_2") (pintype "passive"))
      (node (ref "C114") (pin "1") (pinfunction "1_1") (pintype "passive"))
      (node (ref "C115") (pin "1") (pinfunction "1_1") (pintype "passive"))
      (node (ref "C116") (pin "1") (pinfunction "1_1") (pintype "passive"))
      (node (ref "C117") (pin "1") (pinfunction "1_1") (pintype "passive"))
      (node (ref "C118") (pin "1") (pinfunction "1_1") (pintype "passive"))
      (node (ref "C33") (pin "1") (pinfunction "1_1") (pintype "passive"))
      (node (ref "C34") (pin "1") (pinfunction "1_1") (pintype "passive"))
      (node (ref "C35") (pin "1") (pinfunction "1_1") (pintype "passive"))
      (node (ref "C36") (pin "1") (pinfunction "1_1") (pintype "passive"))
      (node (ref "C37") (pin "1") (pinfunction "1_1") (pintype "passive"))
      (node (ref "C38") (pin "1") (pinfunction "1_1") (pintype "passive"))
      (node (ref "C40") (pin "1") (pinfunction "1_1") (pintype "passive"))
      (node (ref "C41") (pin "1") (pinfunction "1_1") (pintype "passive"))
      (node (ref "C42") (pin "1") (pinfunction "1_1") (pintype "passive"))
      (node (ref "C44") (pin "1") (pinfunction "1_1") (pintype "passive"))
      (node (ref "C45") (pin "1") (pinfunction "1_1") (pintype "passive"))
      (node (ref "C46") (pin "1") (pinfunction "1_1") (pintype "passive"))
      (node (ref "C47") (pin "1") (pinfunction "1_1") (pintype "passive"))
      (node (ref "C48") (pin "1") (pinfunction "1_1") (pintype "passive"))
      (node (ref "C49") (pin "1") (pinfunction "1_1") (pintype "passive"))
      (node (ref "C52") (pin "1") (pinfunction "1_1") (pintype "passive"))
      (node (ref "C53") (pin "1") (pinfunction "1_1") (pintype "passive"))
      (node (ref "C54") (pin "1") (pinfunction "1_1") (pintype "passive"))
      (node (ref "C55") (pin "1") (pinfunction "1_1") (pintype "passive"))
      (node (ref "C56") (pin "1") (pinfunction "1_1") (pintype "passive"))
      (node (ref "C58") (pin "1") (pinfunction "1_1") (pintype "passive"))
      (node (ref "C59") (pin "1") (pinfunction "1_1") (pintype "passive"))
      (node (ref "C60") (pin "1") (pinfunction "1_1") (pintype "passive"))
      (node (ref "C61") (pin "1") (pinfunction "1_1") (pintype "passive"))
      (node (ref "C62") (pin "1") (pinfunction "1_1") (pintype "passive"))
      (node (ref "C63") (pin "1") (pinfunction "1_1") (pintype "passive"))
      (node (ref "C64") (pin "1") (pinfunction "1_1") (pintype "passive"))
      (node (ref "C65") (pin "1") (pinfunction "1_1") (pintype "passive"))
      (node (ref "C66") (pin "1") (pinfunction "1_1") (pintype "passive"))
      (node (ref "C67") (pin "1") (pinfunction "1_1") (pintype "passive"))
      (node (ref "C68") (pin "1") (pinfunction "1_1") (pintype "passive"))
      (node (ref "C69") (pin "1") (pinfunction "1_1") (pintype "passive"))
      (node (ref "C70") (pin "1") (pinfunction "1_1") (pintype "passive"))
      (node (ref "C77") (pin "2") (pinfunction "2_2") (pintype "passive"))
      (node (ref "C78") (pin "2") (pinfunction "2_2") (pintype "passive"))
      (node (ref "C79") (pin "2") (pinfunction "2_2") (pintype "passive"))
      (node (ref "C80") (pin "2") (pinfunction "2_2") (pintype "passive"))
      (node (ref "C81") (pin "1") (pinfunction "1_1") (pintype "passive"))
      (node (ref "C82") (pin "1") (pinfunction "1_1") (pintype "passive"))
      (node (ref "C83") (pin "1") (pinfunction "1_1") (pintype "passive"))
      (node (ref "C84") (pin "1") (pinfunction "1_1") (pintype "passive"))
      (node (ref "C85") (pin "1") (pinfunction "1_1") (pintype "passive"))
      (node (ref "D10") (pin "A") (pinfunction "A_A") (pintype "passive"))
      (node (ref "D6") (pin "C") (pinfunction "C_C") (pintype "passive"))
      (node (ref "D9") (pin "A") (pinfunction "A_A") (pintype "passive"))
      (node (ref "J12") (pin "2") (pintype "passive"))
      (node (ref "J12") (pin "3") (pintype "passive"))
      (node (ref "J13") (pin "2") (pinfunction "2_2") (pintype "passive"))
      (node (ref "J13") (pin "3") (pinfunction "3_3") (pintype "passive"))
      (node (ref "Q10") (pin "S") (pinfunction "S_S") (pintype "passive"))
      (node (ref "Q12") (pin "S") (pinfunction "S_S") (pintype "passive"))
      (node (ref "Q13") (pin "S") (pinfunction "S_S") (pintype "passive"))
      (node (ref "Q14") (pin "S") (pinfunction "S_S") (pintype "passive"))
      (node (ref "Q15") (pin "S") (pinfunction "S_S") (pintype "passive"))
      (node (ref "Q20") (pin "S") (pinfunction "S_S") (pintype "passive"))
      (node (ref "Q21") (pin "S") (pinfunction "S_S") (pintype "passive"))
      (node (ref "Q5") (pin "S") (pinfunction "S_S") (pintype "passive"))
      (node (ref "Q6") (pin "S") (pinfunction "S_S") (pintype "passive"))
      (node (ref "Q7") (pin "S") (pinfunction "S_S") (pintype "passive"))
      (node (ref "Q8") (pin "S") (pinfunction "S_S") (pintype "passive"))
      (node (ref "Q9") (pin "S") (pinfunction "S_S") (pintype "passive"))
      (node (ref "R100") (pin "1") (pinfunction "1_1") (pintype "passive"))
      (node (ref "R101") (pin "1") (pinfunction "1_1") (pintype "passive"))
      (node (ref "R57") (pin "2") (pinfunction "2_2") (pintype "passive"))
      (node (ref "R61") (pin "2") (pinfunction "2_2") (pintype "passive"))
      (node (ref "R67") (pin "1") (pinfunction "1_1") (pintype "passive"))
      (node (ref "R68") (pin "2") (pinfunction "2_2") (pintype "passive"))
      (node (ref "R74") (pin "1") (pinfunction "1_1") (pintype "passive"))
      (node (ref "R75") (pin "1") (pinfunction "1_1") (pintype "passive"))
      (node (ref "R79") (pin "1") (pinfunction "1_1") (pintype "passive"))
      (node (ref "R81") (pin "2") (pinfunction "2_2") (pintype "passive"))
      (node (ref "R82") (pin "1") (pinfunction "1_1") (pintype "passive"))
      (node (ref "R93") (pin "1") (pinfunction "1_1") (pintype "passive"))
      (node (ref "R96") (pin "1") (pinfunction "1_1") (pintype "passive"))
      (node (ref "R97") (pin "1") (pinfunction "1_1") (pintype "passive"))
      (node (ref "R98") (pin "2") (pinfunction "2_2") (pintype "passive"))
      (node (ref "R99") (pin "2") (pinfunction "2_2") (pintype "passive"))
      (node (ref "U10") (pin "11") (pinfunction "PGND2_11") (pintype "power_in"))
      (node (ref "U10") (pin "14") (pinfunction "PGND3_14") (pintype "power_in"))
      (node (ref "U10") (pin "21") (pinfunction "AGND_21") (pintype "power_in"))
      (node (ref "U10") (pin "27") (pinfunction "PGND1_27") (pintype "power_in"))
      (node (ref "U10") (pin "33") (pinfunction "PAD_33") (pintype "power_in"))
      (node (ref "U11") (pin "1") (pinfunction "GND_1") (pintype "power_in"))
      (node (ref "U12") (pin "14") (pinfunction "CMPIN_14") (pintype "input"))
      (node (ref "U12") (pin "27") (pinfunction "PGND_27") (pintype "power_in"))
      (node (ref "U12") (pin "33") (pinfunction "PAD_33") (pintype "power_in"))
    )
    (net (code "20") (name "Net-(C34-Pad2)") (class "Default")
      (node (ref "C34") (pin "2") (pinfunction "2_2") (pintype "passive"))
      (node (ref "R54") (pin "1") (pinfunction "1_1") (pintype "passive"))
    )
    (net (code "21") (name "Net-(C45-Pad2)") (class "Default")
      (node (ref "C45") (pin "2") (pinfunction "2_2") (pintype "passive"))
      (node (ref "R58") (pin "1") (pinfunction "1_1") (pintype "passive"))
    )
    (net (code "22") (name "Net-(C59-Pad2)") (class "Default")
      (node (ref "C59") (pin "2") (pinfunction "2_2") (pintype "passive"))
      (node (ref "R64") (pin "1") (pinfunction "1_1") (pintype "passive"))
    )
    (net (code "23") (name "Net-(C71-Pad1)") (class "Default")
      (node (ref "C71") (pin "1") (pinfunction "1_1") (pintype "passive"))
      (node (ref "Q16") (pin "G") (pinfunction "G_G") (pintype "passive"))
      (node (ref "R93") (pin "2") (pinfunction "2_2") (pintype "passive"))
    )
    (net (code "24") (name "Net-(C72-Pad1)") (class "Default")
      (node (ref "C72") (pin "1") (pinfunction "1_1") (pintype "passive"))
      (node (ref "R89") (pin "S2") (pinfunction "S2_S2") (pintype "passive"))
      (node (ref "R95") (pin "2") (pinfunction "2_2") (pintype "passive"))
    )
    (net (code "25") (name "Net-(C72-Pad2)") (class "Default")
      (node (ref "C72") (pin "2") (pinfunction "2_2") (pintype "passive"))
      (node (ref "C77") (pin "1") (pinfunction "1_1") (pintype "passive"))
      (node (ref "R89") (pin "S1") (pinfunction "S1_S1") (pintype "passive"))
      (node (ref "R94") (pin "2") (pinfunction "2_2") (pintype "passive"))
    )
    (net (code "26") (name "Net-(C75-Pad2)") (class "Default")
      (node (ref "C75") (pin "2") (pinfunction "2_2") (pintype "passive"))
      (node (ref "R96") (pin "2") (pinfunction "2_2") (pintype "passive"))
    )
    (net (code "27") (name "Net-(C76-Pad2)") (class "Default")
      (node (ref "C76") (pin "2") (pinfunction "2_2") (pintype "passive"))
      (node (ref "R97") (pin "2") (pinfunction "2_2") (pintype "passive"))
    )
    (net (code "28") (name "Net-(D4-PadA1)") (class "Default")
      (node (ref "D4") (pin "A1") (pinfunction "A1_A1") (pintype "passive"))
      (node (ref "D5") (pin "C") (pinfunction "C_C") (pintype "passive"))
      (node (ref "Q13") (pin "D") (pinfunction "D_D") (pintype "passive"))
      (node (ref "R71") (pin "2") (pinfunction "2_2") (pintype "passive"))
    )
    (net (code "29") (name "Net-(D4-PadA2)") (class "Default")
      (node (ref "D4") (pin "A2") (pinfunction "A2_A2") (pintype "passive"))
      (node (ref "Q10") (pin "G") (pinfunction "G_G") (pintype "passive"))
      (node (ref "Q9") (pin "D") (pinfunction "D_D") (pintype "passive"))
      (node (ref "R70") (pin "2") (pinfunction "2_2") (pintype "passive"))
    )
    (net (code "30") (name "Net-(D6-PadA)") (class "Default")
      (node (ref "D6") (pin "A") (pinfunction "A_A") (pintype "passive"))
      (node (ref "R76") (pin "1") (pinfunction "1_1") (pintype "passive"))
    )
    (net (code "31") (name "Net-(D7-PadA)") (class "Default")
      (node (ref "D7") (pin "A") (pinfunction "A_A") (pintype "passive"))
      (node (ref "R77") (pin "1") (pinfunction "1_1") (pintype "passive"))
    )
    (net (code "32") (name "Net-(D7-PadC)") (class "Default")
      (node (ref "D7") (pin "C") (pinfunction "C_C") (pintype "passive"))
      (node (ref "Q14") (pin "D") (pinfunction "D_D") (pintype "passive"))
    )
    (net (code "33") (name "Net-(D8-PadA)") (class "Default")
      (node (ref "D8") (pin "A") (pinfunction "A_A") (pintype "passive"))
      (node (ref "R78") (pin "1") (pinfunction "1_1") (pintype "passive"))
    )
    (net (code "34") (name "Net-(D8-PadC)") (class "Default")
      (node (ref "D8") (pin "C") (pinfunction "C_C") (pintype "passive"))
      (node (ref "Q15") (pin "D") (pinfunction "D_D") (pintype "passive"))
    )
    (net (code "35") (name "Net-(J12-Pad1)") (class "Default")
      (node (ref "J12") (pin "1") (pintype "passive"))
      (node (ref "R84") (pin "2") (pinfunction "2_2") (pintype "passive"))
    )
    (net (code "36") (name "Net-(J12-Pad4)") (class "Default")
      (node (ref "J12") (pin "4") (pintype "passive"))
      (node (ref "R83") (pin "2") (pinfunction "2_2") (pintype "passive"))
    )
    (net (code "37") (name "Net-(Q5-PadD)") (class "Default")
      (node (ref "Q5") (pin "D") (pinfunction "D_D") (pintype "passive"))
      (node (ref "R55") (pin "2") (pinfunction "2_2") (pintype "passive"))
    )
    (net (code "38") (name "Net-(Q6-PadD)") (class "Default")
      (node (ref "Q6") (pin "D") (pinfunction "D_D") (pintype "passive"))
      (node (ref "R59") (pin "2") (pinfunction "2_2") (pintype "passive"))
    )
    (net (code "39") (name "Net-(Q7-PadD)") (class "Default")
      (node (ref "Q7") (pin "D") (pinfunction "D_D") (pintype "passive"))
      (node (ref "R65") (pin "2") (pinfunction "2_2") (pintype "passive"))
    )
    (net (code "40") (name "Net-(Q8-PadD)") (class "Default")
      (node (ref "Q8") (pin "D") (pinfunction "D_D") (pintype "passive"))
      (node (ref "R69") (pin "1") (pinfunction "1_1") (pintype "passive"))
    )
    (net (code "41") (name "Net-(Q11-PadG)") (class "Default")
      (node (ref "Q11") (pin "G") (pinfunction "G_G") (pintype "passive"))
      (node (ref "Q12") (pin "D") (pinfunction "D_D") (pintype "passive"))
      (node (ref "R80") (pin "1") (pinfunction "1_1") (pintype "passive"))
    )
    (net (code "42") (name "Net-(R88-PadS1)") (class "Default")
      (node (ref "R88") (pin "S1") (pinfunction "S1_S1") (pintype "passive"))
      (node (ref "R91") (pin "2") (pinfunction "2_2") (pintype "passive"))
    )
    (net (code "43") (name "Net-(R88-PadS2)") (class "Default")
      (node (ref "R88") (pin "S2") (pinfunction "S2_S2") (pintype "passive"))
      (node (ref "R90") (pin "2") (pinfunction "2_2") (pintype "passive"))
    )
    (net (code "44") (name "Net-(U10A-EN1)") (class "Default")
      (node (ref "C64") (pin "2") (pinfunction "2_2") (pintype "passive"))
      (node (ref "R72") (pin "1") (pinfunction "1_1") (pintype "passive"))
      (node (ref "U10") (pin "31") (pinfunction "EN1_31") (pintype "input"))
      (node (ref "U10") (pin "32") (pinfunction "EN2_32") (pintype "input"))
      (node (ref "U10") (pin "4") (pinfunction "MODE_4") (pintype "input"))
      (node (ref "U10") (pin "5") (pinfunction "V7V_5") (pintype "power_in"))
    )
    (net (code "45") (name "Net-(U10A-EN3)") (class "Default")
      (node (ref "D5") (pin "A2") (pinfunction "A2_A2") (pintype "passive"))
      (node (ref "U10") (pin "1") (pinfunction "EN3_1") (pintype "input"))
    )
    (net (code "46") (name "Net-(U10A-ROSC)") (class "Default")
      (node (ref "R75") (pin "2") (pinfunction "2_2") (pintype "passive"))
      (node (ref "U10") (pin "20") (pinfunction "ROSC_20") (pintype "input"))
    )
    (net (code "47") (name "Net-(U10A-VDIV)") (class "Default")
      (node (ref "R73") (pin "1") (pinfunction "1_1") (pintype "passive"))
      (node (ref "R79") (pin "2") (pinfunction "2_2") (pintype "passive"))
      (node (ref "U10") (pin "30") (pinfunction "VDIV_30") (pintype "input"))
    )
    (net (code "48") (name "Net-(U10B-BST1)") (class "Default")
      (node (ref "C32") (pin "2") (pinfunction "2_2") (pintype "passive"))
      (node (ref "U10") (pin "25") (pinfunction "BST1_25") (pintype "power_in"))
    )
    (net (code "49") (name "Net-(U10B-COMP1)") (class "Default")
      (node (ref "C35") (pin "2") (pinfunction "2_2") (pintype "passive"))
      (node (ref "R54") (pin "2") (pinfunction "2_2") (pintype "passive"))
      (node (ref "U10") (pin "23") (pinfunction "COMP1_23") (pintype "passive"))
    )
    (net (code "50") (name "Net-(U10B-FB1)") (class "Default")
      (node (ref "R56") (pin "2") (pinfunction "2_2") (pintype "passive"))
      (node (ref "R57") (pin "1") (pinfunction "1_1") (pintype "passive"))
      (node (ref "U10") (pin "22") (pinfunction "FB1_22") (pintype "input"))
    )
    (net (code "51") (name "Net-(U10B-LX1)") (class "Default")
      (node (ref "C32") (pin "1") (pinfunction "1_1") (pintype "passive"))
      (node (ref "L1") (pin "1") (pinfunction "1_1") (pintype "passive"))
      (node (ref "U10") (pin "26") (pinfunction "LX1_26") (pintype "power_in"))
    )
    (net (code "52") (name "Net-(U10B-SS1)") (class "Default")
      (node (ref "C36") (pin "2") (pinfunction "2_2") (pintype "passive"))
      (node (ref "U10") (pin "24") (pinfunction "SS1_24") (pintype "passive"))
    )
    (net (code "53") (name "Net-(U10C-BST2)") (class "Default")
      (node (ref "C43") (pin "2") (pinfunction "2_2") (pintype "passive"))
      (node (ref "U10") (pin "9") (pinfunction "BST2_9") (pintype "power_in"))
    )
    (net (code "54") (name "Net-(U10C-COMP2)") (class "Default")
      (node (ref "C46") (pin "2") (pinfunction "2_2") (pintype "passive"))
      (node (ref "R58") (pin "2") (pinfunction "2_2") (pintype "passive"))
      (node (ref "U10") (pin "7") (pinfunction "COMP2_7") (pintype "passive"))
    )
    (net (code "55") (name "Net-(U10C-FB2)") (class "Default")
      (node (ref "R60") (pin "2") (pinfunction "2_2") (pintype "passive"))
      (node (ref "R61") (pin "1") (pinfunction "1_1") (pintype "passive"))
      (node (ref "U10") (pin "6") (pinfunction "FB2_6") (pintype "input"))
    )
    (net (code "56") (name "Net-(U10C-LX2)") (class "Default")
      (node (ref "C43") (pin "1") (pinfunction "1_1") (pintype "passive"))
      (node (ref "L2") (pin "1") (pinfunction "1_1") (pintype "passive"))
      (node (ref "U10") (pin "10") (pinfunction "LX2_10") (pintype "power_in"))
    )
    (net (code "57") (name "Net-(U10C-SS2)") (class "Default")
      (node (ref "C47") (pin "2") (pinfunction "2_2") (pintype "passive"))
      (node (ref "U10") (pin "8") (pinfunction "SS2_8") (pintype "passive"))
    )
    (net (code "58") (name "Net-(U10D-BST3)") (class "Default")
      (node (ref "C51") (pin "2") (pinfunction "2_2") (pintype "passive"))
      (node (ref "U10") (pin "16") (pinfunction "BST3_16") (pintype "power_in"))
    )
    (net (code "59") (name "Net-(U10D-COMP3)") (class "Default")
      (node (ref "C60") (pin "2") (pinfunction "2_2") (pintype "passive"))
      (node (ref "R64") (pin "2") (pinfunction "2_2") (pintype "passive"))
      (node (ref "U10") (pin "18") (pinfunction "COMP3_18") (pintype "passive"))
    )
    (net (code "60") (name "Net-(U10D-FB3)") (class "Default")
      (node (ref "R66") (pin "2") (pinfunction "2_2") (pintype "passive"))
      (node (ref "R68") (pin "1") (pinfunction "1_1") (pintype "passive"))
      (node (ref "U10") (pin "19") (pinfunction "FB3_19") (pintype "input"))
    )
    (net (code "61") (name "Net-(U10D-LX3)") (class "Default")
      (node (ref "C51") (pin "1") (pinfunction "1_1") (pintype "passive"))
      (node (ref "L4") (pin "1") (pinfunction "1_1") (pintype "passive"))
      (node (ref "U10") (pin "15") (pinfunction "LX3_15") (pintype "power_in"))
    )
    (net (code "62") (name "Net-(U10D-SS3)") (class "Default")
      (node (ref "C61") (pin "2") (pinfunction "2_2") (pintype "passive"))
      (node (ref "U10") (pin "17") (pinfunction "SS3_17") (pintype "passive"))
    )
    (net (code "63") (name "Net-(U11-EN)") (class "Default")
      (node (ref "R62") (pin "2") (pinfunction "2_2") (pintype "passive"))
      (node (ref "U11") (pin "5") (pinfunction "EN_5") (pintype "input"))
    )
    (net (code "64") (name "Net-(U11-SW)") (class "Default")
      (node (ref "C50") (pin "1") (pinfunction "1_1") (pintype "passive"))
      (node (ref "L3") (pin "1") (pinfunction "1_1") (pintype "passive"))
      (node (ref "U11") (pin "2") (pinfunction "SW_2") (pintype "power_in"))
    )
    (net (code "65") (name "Net-(U11-VBST)") (class "Default")
      (node (ref "C50") (pin "2") (pinfunction "2_2") (pintype "passive"))
      (node (ref "U11") (pin "6") (pinfunction "VBST_6") (pintype "power_in"))
    )
    (net (code "66") (name "Net-(U11-VFB)") (class "Default")
      (node (ref "C57") (pin "2") (pinfunction "2_2") (pintype "passive"))
      (node (ref "R63") (pin "1") (pinfunction "1_1") (pintype "passive"))
      (node (ref "R67") (pin "2") (pinfunction "2_2") (pintype "passive"))
      (node (ref "U11") (pin "4") (pinfunction "VFB_4") (pintype "passive"))
    )
    (net (code "67") (name "Net-(U12A-ACN)") (class "Default")
      (node (ref "C84") (pin "2") (pinfunction "2_2") (pintype "passive"))
      (node (ref "R91") (pin "1") (pinfunction "1_1") (pintype "passive"))
      (node (ref "U12") (pin "2") (pinfunction "ACN_2") (pintype "input"))
    )
    (net (code "68") (name "Net-(U12A-ACP)") (class "Default")
      (node (ref "C83") (pin "2") (pinfunction "2_2") (pintype "passive"))
      (node (ref "R90") (pin "1") (pinfunction "1_1") (pintype "passive"))
      (node (ref "U12") (pin "3") (pinfunction "ACP_3") (pintype "input"))
    )
    (net (code "69") (name "Net-(U12A-BATDRV)") (class "Default")
      (node (ref "Q19") (pin "G") (pinfunction "G_G") (pintype "passive"))
      (node (ref "U12") (pin "21") (pinfunction "BATDRV_21") (pintype "output"))
    )
    (net (code "70") (name "Net-(U12A-BTST1)") (class "Default")
      (node (ref "C73") (pin "1") (pinfunction "1_1") (pintype "passive"))
      (node (ref "U12") (pin "30") (pinfunction "BTST1_30") (pintype "input"))
    )
    (net (code "71") (name "Net-(U12A-BTST2)") (class "Default")
      (node (ref "C74") (pin "1") (pinfunction "1_1") (pintype "passive"))
      (node (ref "U12") (pin "25") (pinfunction "BTST2_25") (pintype "input"))
    )
    (net (code "72") (name "Net-(U12A-HIDRV1)") (class "Default")
      (node (ref "Q17") (pin "G") (pinfunction "G_G") (pintype "passive"))
      (node (ref "U12") (pin "31") (pinfunction "HIDRV1_31") (pintype "output"))
    )
    (net (code "73") (name "Net-(U12A-HIDRV2)") (class "Default")
      (node (ref "Q18") (pin "G") (pinfunction "G_G") (pintype "passive"))
      (node (ref "U12") (pin "24") (pinfunction "HIDRV2_24") (pintype "output"))
    )
    (net (code "74") (name "Net-(U12A-LODRV1)") (class "Default")
      (node (ref "Q20") (pin "G") (pinfunction "G_G") (pintype "passive"))
      (node (ref "U12") (pin "29") (pinfunction "LODRV1_29") (pintype "output"))
    )
    (net (code "75") (name "Net-(U12A-LODRV2)") (class "Default")
      (node (ref "Q21") (pin "G") (pinfunction "G_G") (pintype "passive"))
      (node (ref "U12") (pin "26") (pinfunction "LODRV2_26") (pintype "output"))
    )
    (net (code "76") (name "Net-(U12A-SRN)") (class "Default")
      (node (ref "R95") (pin "1") (pinfunction "1_1") (pintype "passive"))
      (node (ref "U12") (pin "19") (pinfunction "SRN_19") (pintype "input"))
    )
    (net (code "77") (name "Net-(U12A-SRP)") (class "Default")
      (node (ref "R94") (pin "1") (pinfunction "1_1") (pintype "passive"))
      (node (ref "U12") (pin "20") (pinfunction "SRP_20") (pintype "input"))
    )
    (net (code "78") (name "Net-(U12A-VBUS)") (class "Default")
      (node (ref "C85") (pin "2") (pinfunction "2_2") (pintype "passive"))
      (node (ref "R92") (pin "1") (pinfunction "1_1") (pintype "passive"))
      (node (ref "U12") (pin "1") (pinfunction "VBUS_1") (pintype "power_in"))
    )
    (net (code "79") (name "Net-(U12B-BATPRESZ)") (class "Default")
      (node (ref "R86") (pin "2") (pinfunction "2_2") (pintype "passive"))
      (node (ref "R99") (pin "1") (pinfunction "1_1") (pintype "passive"))
      (node (ref "U12") (pin "18") (pinfunction "BATPRESZ_18") (pintype "input"))
    )
    (net (code "80") (name "Net-(U12B-COMP1)") (class "Default")
      (node (ref "C76") (pin "1") (pinfunction "1_1") (pintype "passive"))
      (node (ref "C79") (pin "1") (pinfunction "1_1") (pintype "passive"))
      (node (ref "U12") (pin "16") (pinfunction "COMP1_16") (pintype "input"))
    )
    (net (code "81") (name "Net-(U12B-COMP2)") (class "Default")
      (node (ref "C75") (pin "1") (pinfunction "1_1") (pintype "passive"))
      (node (ref "C78") (pin "1") (pinfunction "1_1") (pintype "passive"))
      (node (ref "U12") (pin "17") (pinfunction "COMP2_17") (pintype "input"))
    )
    (net (code "82") (name "Net-(U12B-IADPT)") (class "Default")
      (node (ref "C82") (pin "2") (pinfunction "2_2") (pintype "passive"))
      (node (ref "R101") (pin "2") (pinfunction "2_2") (pintype "passive"))
      (node (ref "U12") (pin "8") (pinfunction "IADPT_8") (pintype "output"))
    )
    (net (code "83") (name "Net-(U12B-IBAT)") (class "Default")
      (node (ref "C81") (pin "2") (pinfunction "2_2") (pintype "passive"))
      (node (ref "U12") (pin "9") (pinfunction "IBAT_9") (pintype "output"))
    )
    (net (code "84") (name "Net-(U12B-ILIM_HIZ)") (class "Default")
      (node (ref "R85") (pin "2") (pinfunction "2_2") (pintype "passive"))
      (node (ref "R98") (pin "1") (pinfunction "1_1") (pintype "passive"))
      (node (ref "U12") (pin "6") (pinfunction "ILIM_HIZ_6") (pintype "input"))
    )
    (net (code "85") (name "Net-(U12B-PSYS)") (class "Default")
      (node (ref "R100") (pin "2") (pinfunction "2_2") (pintype "passive"))
      (node (ref "U12") (pin "10") (pinfunction "PSYS_10") (pintype "output"))
    )
    (net (code "86") (name "Net-(U12B-REGN)") (class "Default")
      (node (ref "C80") (pin "1") (pinfunction "1_1") (pintype "passive"))
      (node (ref "R87") (pin "1") (pinfunction "1_1") (pintype "passive"))
      (node (ref "U12") (pin "28") (pinfunction "REGN_28") (pintype "power_in"))
    )
    (net (code "87") (name "Net-(U12B-VDDA)") (class "Default")
      (node (ref "C70") (pin "2") (pinfunction "2_2") (pintype "passive"))
      (node (ref "R85") (pin "1") (pinfunction "1_1") (pintype "passive"))
      (node (ref "R86") (pin "1") (pinfunction "1_1") (pintype "passive"))
      (node (ref "R87") (pin "2") (pinfunction "2_2") (pintype "passive"))
      (node (ref "U12") (pin "7") (pinfunction "VDDA_7") (pintype "power_in"))
    )
    (net (code "88") (name "VDD_1V8_SYS") (class "Default")
      (node (ref "C62") (pin "2") (pinfunction "2_2") (pintype "passive"))
      (node (ref "C63") (pin "2") (pinfunction "2_2") (pintype "passive"))
      (node (ref "L4") (pin "2") (pinfunction "2_2") (pintype "passive"))
      (node (ref "R65") (pin "1") (pinfunction "1_1") (pintype "passive"))
      (node (ref "R66") (pin "1") (pinfunction "1_1") (pintype "passive"))
    )
    (net (code "89") (name "VDD_3V3_MCU") (class "Default")
      (node (ref "C54") (pin "2") (pinfunction "2_2") (pintype "passive"))
      (node (ref "C55") (pin "2") (pinfunction "2_2") (pintype "passive"))
      (node (ref "C56") (pin "2") (pinfunction "2_2") (pintype "passive"))
      (node (ref "C57") (pin "1") (pinfunction "1_1") (pintype "passive"))
      (node (ref "L3") (pin "2") (pinfunction "2_2") (pintype "passive"))
      (node (ref "R63") (pin "2") (pinfunction "2_2") (pintype "passive"))
      (node (ref "R76") (pin "2") (pinfunction "2_2") (pintype "passive"))
    )
    (net (code "90") (name "VDD_3V3_STBY") (class "Default")
      (node (ref "C66") (pin "2") (pinfunction "2_2") (pintype "passive"))
      (node (ref "C67") (pin "2") (pinfunction "2_2") (pintype "passive"))
      (node (ref "C68") (pin "2") (pinfunction "2_2") (pintype "passive"))
      (node (ref "C69") (pin "2") (pinfunction "2_2") (pintype "passive"))
      (node (ref "Q11") (pin "D") (pinfunction "D_D") (pintype "passive"))
      (node (ref "R69") (pin "2") (pinfunction "2_2") (pintype "passive"))
    )
    (net (code "91") (name "VDD_3V3_SYS") (class "Default")
      (node (ref "C48") (pin "2") (pinfunction "2_2") (pintype "passive"))
      (node (ref "C49") (pin "2") (pinfunction "2_2") (pintype "passive"))
      (node (ref "L2") (pin "2") (pinfunction "2_2") (pintype "passive"))
      (node (ref "Q11") (pin "S") (pinfunction "S_S") (pintype "passive"))
      (node (ref "R59") (pin "1") (pinfunction "1_1") (pintype "passive"))
      (node (ref "R60") (pin "1") (pinfunction "1_1") (pintype "passive"))
      (node (ref "R80") (pin "2") (pinfunction "2_2") (pintype "passive"))
    )
    (net (code "92") (name "VDD_5V0_SYS") (class "Default")
      (node (ref "C37") (pin "2") (pinfunction "2_2") (pintype "passive"))
      (node (ref "C38") (pin "2") (pinfunction "2_2") (pintype "passive"))
      (node (ref "L1") (pin "2") (pinfunction "2_2") (pintype "passive"))
      (node (ref "R55") (pin "1") (pinfunction "1_1") (pintype "passive"))
      (node (ref "R56") (pin "1") (pinfunction "1_1") (pintype "passive"))
    )
    (net (code "93") (name "VIN_NVM") (class "Default")
      (node (ref "C113") (pin "1") (pinfunction "1_1") (pintype "passive"))
      (node (ref "C40") (pin "2") (pinfunction "2_2") (pintype "passive"))
      (node (ref "C41") (pin "2") (pinfunction "2_2") (pintype "passive"))
      (node (ref "C42") (pin "2") (pinfunction "2_2") (pintype "passive"))
      (node (ref "FB11") (pin "2") (pinfunction "2_2") (pintype "passive"))
      (node (ref "FB12") (pin "2") (pinfunction "2_2") (pintype "passive"))
      (node (ref "FB13") (pin "2") (pinfunction "2_2") (pintype "passive"))
    )
    (net (code "94") (name "VIN_PSU") (class "Default")
      (node (ref "C116") (pin "2") (pinfunction "2_2") (pintype "passive"))
      (node (ref "C117") (pin "2") (pinfunction "2_2") (pintype "passive"))
      (node (ref "C118") (pin "2") (pinfunction "2_2") (pintype "passive"))
      (node (ref "C33") (pin "2") (pinfunction "2_2") (pintype "passive"))
      (node (ref "C44") (pin "2") (pinfunction "2_2") (pintype "passive"))
      (node (ref "C52") (pin "2") (pinfunction "2_2") (pintype "passive"))
      (node (ref "C53") (pin "2") (pinfunction "2_2") (pintype "passive"))
      (node (ref "C58") (pin "2") (pinfunction "2_2") (pintype "passive"))
      (node (ref "C65") (pin "2") (pinfunction "2_2") (pintype "passive"))
      (node (ref "FB11") (pin "1") (pinfunction "1_1") (pintype "passive"))
      (node (ref "FB12") (pin "1") (pinfunction "1_1") (pintype "passive"))
      (node (ref "FB13") (pin "1") (pinfunction "1_1") (pintype "passive"))
      (node (ref "Q18") (pin "D") (pinfunction "D_D") (pintype "passive"))
      (node (ref "Q19") (pin "D") (pinfunction "D_D") (pintype "passive"))
      (node (ref "R62") (pin "1") (pinfunction "1_1") (pintype "passive"))
      (node (ref "R70") (pin "1") (pinfunction "1_1") (pintype "passive"))
      (node (ref "R71") (pin "1") (pinfunction "1_1") (pintype "passive"))
      (node (ref "R73") (pin "2") (pinfunction "2_2") (pintype "passive"))
      (node (ref "R77") (pin "2") (pinfunction "2_2") (pintype "passive"))
      (node (ref "R78") (pin "2") (pinfunction "2_2") (pintype "passive"))
      (node (ref "U10") (pin "12") (pinfunction "PVIN2_12") (pintype "power_in"))
      (node (ref "U10") (pin "13") (pinfunction "PVIN3_13") (pintype "power_in"))
      (node (ref "U10") (pin "28") (pinfunction "PVIN1_28") (pintype "power_in"))
      (node (ref "U10") (pin "29") (pinfunction "VIN_29") (pintype "power_in"))
      (node (ref "U11") (pin "3") (pinfunction "VIN_3") (pintype "power_in"))
      (node (ref "U12") (pin "22") (pinfunction "VSYS_22") (pintype "input"))
    )
    (net (code "95") (name "unconnected-(D5-PadA1)") (class "Default")
      (node (ref "D5") (pin "A1") (pinfunction "A1_A1") (pintype "passive"))
    )
    (net (code "96") (name "unconnected-(U12B-CMPOUT-Pad15)") (class "Default")
      (node (ref "U12") (pin "15") (pinfunction "CMPOUT_15") (pintype "open_collector"))
    )
  )
)
